# PWM_Drivers.net
KiCad netlist of a schematic drawn in Altium Designer
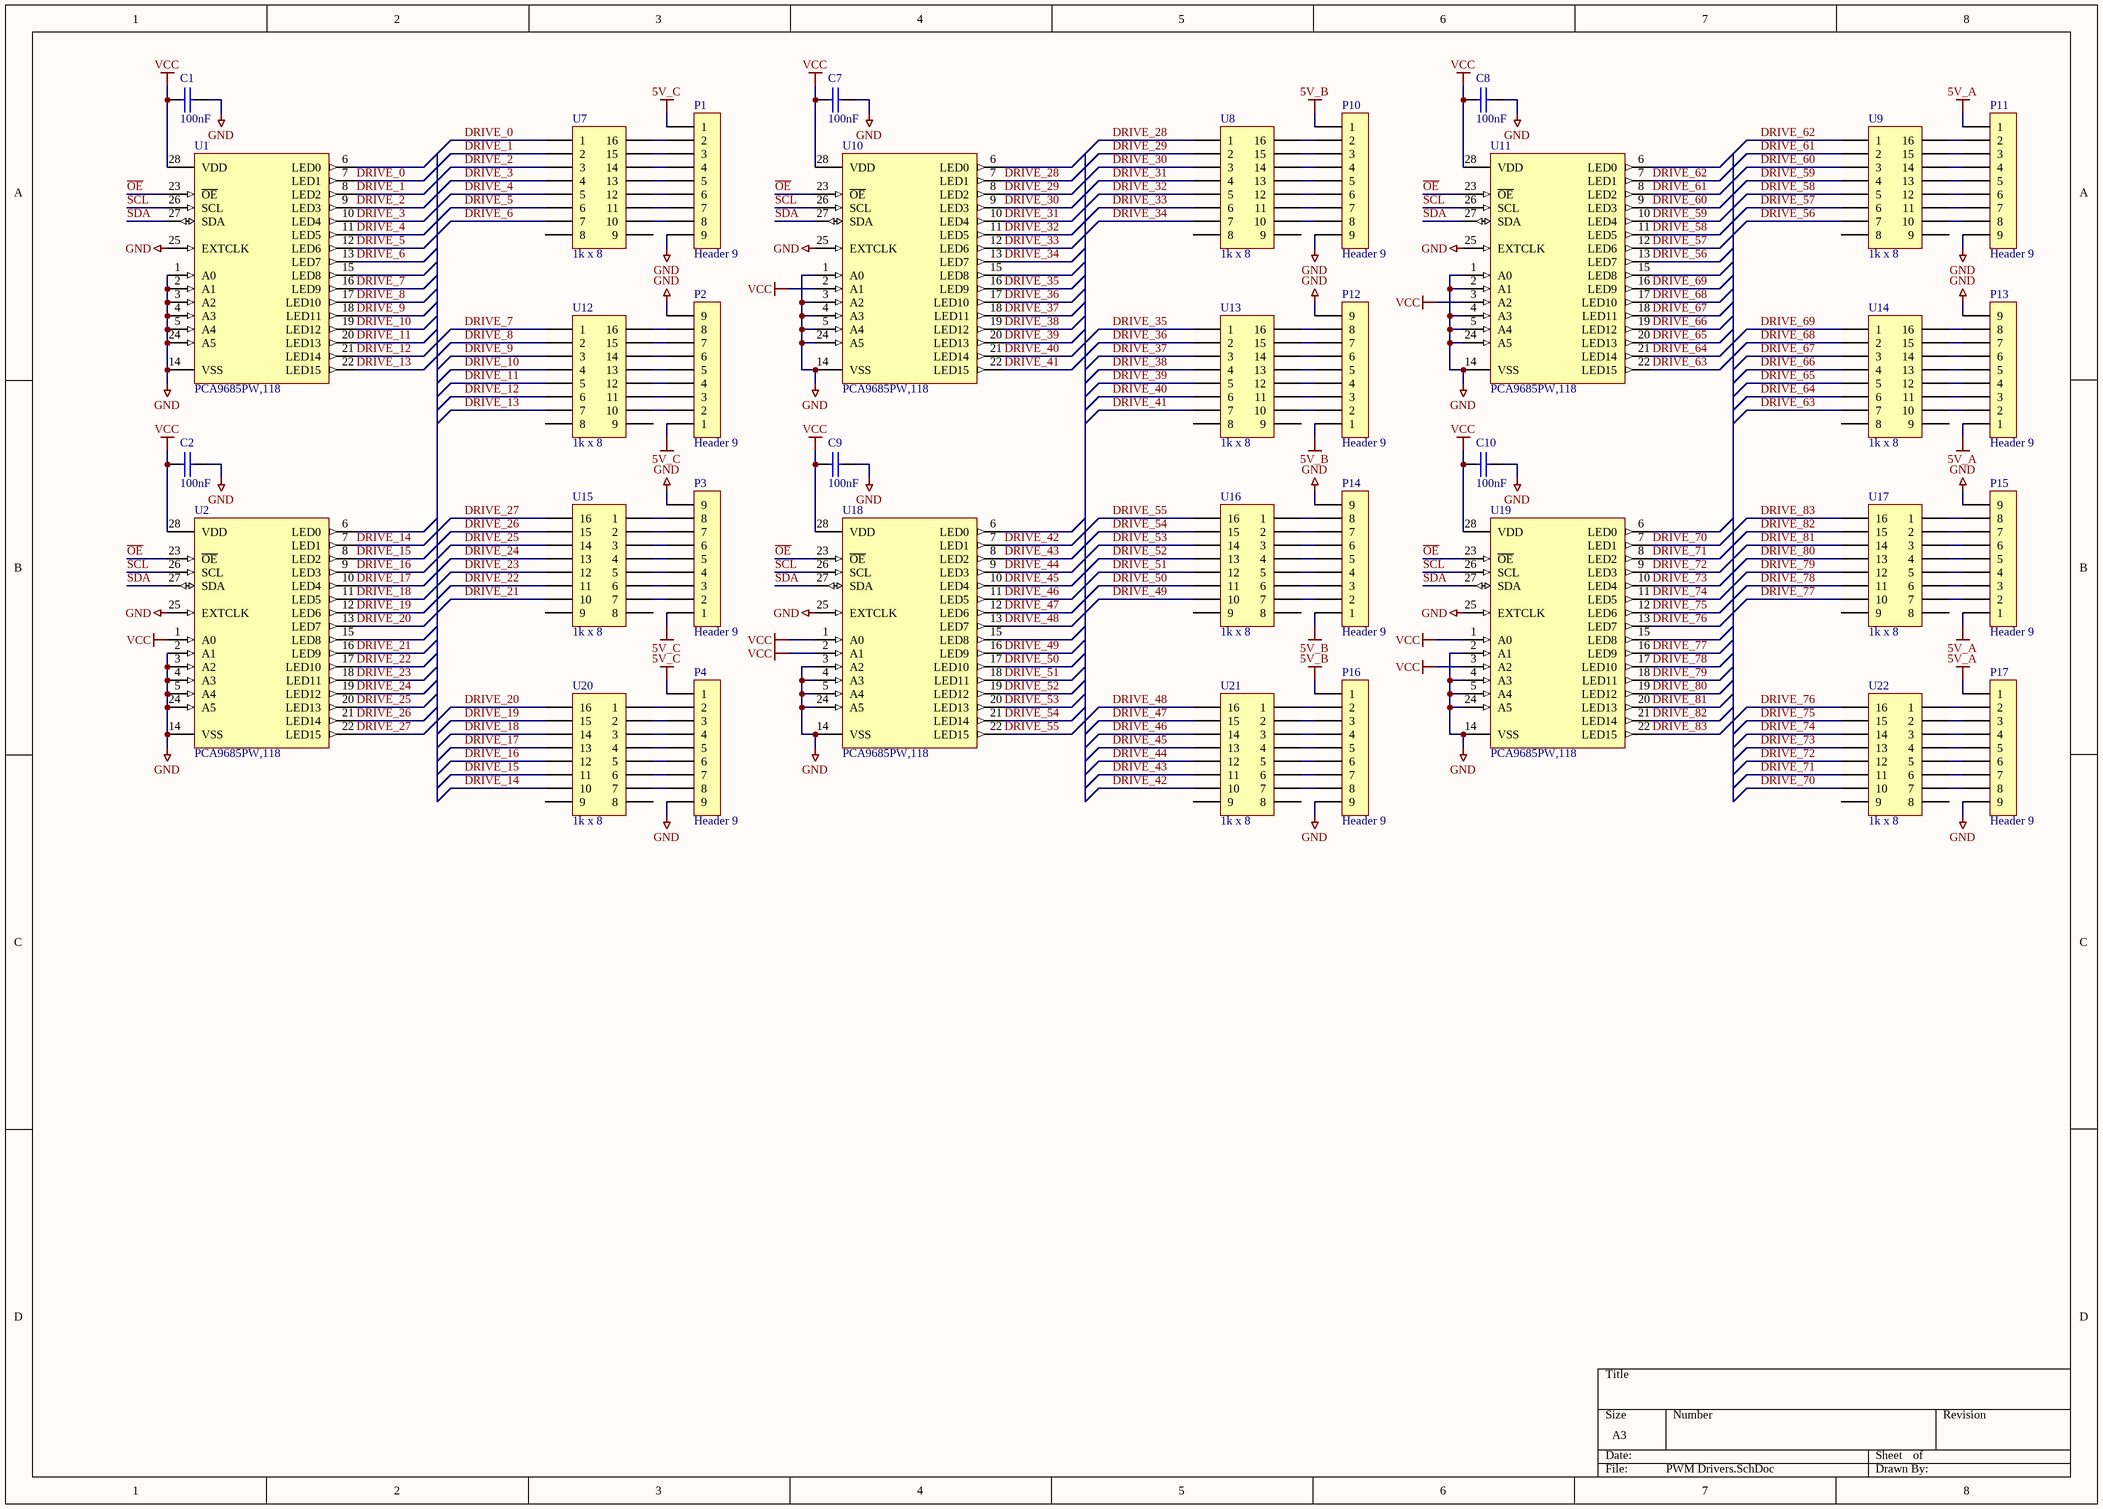
[diagram p0: PWM Drivers.SchDoc]

(export (version "E")
  (design (tool "Eeschema 10.0.6"))
  (components
    (comp (ref "C1")
      (value "100nF")
      (footprint "CAPACITOR 0805")
      (description "CAPACITOR SMD 0603")
      (fields (field (name "MOUSER PART NO.") "81-GCM188R71C104KA7D") (field (name "MANUFACTURER") "Murata"))
      (libsource (lib "Mi-Call Schematic") (part "CAP"))
    )
    (comp (ref "C2")
      (value "100nF")
      (footprint "CAPACITOR 0805")
      (description "CAPACITOR SMD 0603")
      (fields (field (name "MOUSER PART NO.") "81-GCM188R71C104KA7D") (field (name "MANUFACTURER") "Murata"))
      (libsource (lib "Mi-Call Schematic") (part "CAP"))
    )
    (comp (ref "C7")
      (value "100nF")
      (footprint "CAPACITOR 0805")
      (description "CAPACITOR SMD 0603")
      (fields (field (name "MOUSER PART NO.") "81-GCM188R71C104KA7D") (field (name "MANUFACTURER") "Murata"))
      (libsource (lib "Mi-Call Schematic") (part "CAP"))
    )
    (comp (ref "C8")
      (value "100nF")
      (footprint "CAPACITOR 0805")
      (description "CAPACITOR SMD 0603")
      (fields (field (name "MOUSER PART NO.") "81-GCM188R71C104KA7D") (field (name "MANUFACTURER") "Murata"))
      (libsource (lib "Mi-Call Schematic") (part "CAP"))
    )
    (comp (ref "C9")
      (value "100nF")
      (footprint "CAPACITOR 0805")
      (description "CAPACITOR SMD 0603")
      (fields (field (name "MOUSER PART NO.") "81-GCM188R71C104KA7D") (field (name "MANUFACTURER") "Murata"))
      (libsource (lib "Mi-Call Schematic") (part "CAP"))
    )
    (comp (ref "C10")
      (value "100nF")
      (footprint "CAPACITOR 0805")
      (description "CAPACITOR SMD 0603")
      (fields (field (name "MOUSER PART NO.") "81-GCM188R71C104KA7D") (field (name "MANUFACTURER") "Murata"))
      (libsource (lib "Mi-Call Schematic") (part "CAP"))
    )
    (comp (ref "P1")
      (value "Header 9")
      (footprint "SOCKET 1x9")
      (description "Header, 9-Pin")
      (fields (field (name "PUBLISHER") "Altium Limited"))
      (libsource (lib "LED TAIL LIGHTS") (part "Header 9"))
    )
    (comp (ref "P2")
      (value "Header 9")
      (footprint "SOCKET 1x9")
      (description "Header, 9-Pin")
      (fields (field (name "PUBLISHER") "Altium Limited"))
      (libsource (lib "") (part "Header 9_1"))
    )
    (comp (ref "P3")
      (value "Header 9")
      (footprint "SOCKET 1x9")
      (description "Header, 9-Pin")
      (fields (field (name "PUBLISHER") "Altium Limited"))
      (libsource (lib "") (part "Header 9_1"))
    )
    (comp (ref "P4")
      (value "Header 9")
      (footprint "SOCKET 1x9")
      (description "Header, 9-Pin")
      (fields (field (name "PUBLISHER") "Altium Limited"))
      (libsource (lib "LED TAIL LIGHTS") (part "Header 9"))
    )
    (comp (ref "P10")
      (value "Header 9")
      (footprint "SOCKET 1x9")
      (description "Header, 9-Pin")
      (fields (field (name "PUBLISHER") "Altium Limited"))
      (libsource (lib "LED TAIL LIGHTS") (part "Header 9"))
    )
    (comp (ref "P11")
      (value "Header 9")
      (footprint "SOCKET 1x9")
      (description "Header, 9-Pin")
      (fields (field (name "PUBLISHER") "Altium Limited"))
      (libsource (lib "LED TAIL LIGHTS") (part "Header 9"))
    )
    (comp (ref "P12")
      (value "Header 9")
      (footprint "SOCKET 1x9")
      (description "Header, 9-Pin")
      (fields (field (name "PUBLISHER") "Altium Limited"))
      (libsource (lib "") (part "Header 9_1"))
    )
    (comp (ref "P13")
      (value "Header 9")
      (footprint "SOCKET 1x9")
      (description "Header, 9-Pin")
      (fields (field (name "PUBLISHER") "Altium Limited"))
      (libsource (lib "") (part "Header 9_1"))
    )
    (comp (ref "P14")
      (value "Header 9")
      (footprint "SOCKET 1x9")
      (description "Header, 9-Pin")
      (fields (field (name "PUBLISHER") "Altium Limited"))
      (libsource (lib "") (part "Header 9_1"))
    )
    (comp (ref "P15")
      (value "Header 9")
      (footprint "SOCKET 1x9")
      (description "Header, 9-Pin")
      (fields (field (name "PUBLISHER") "Altium Limited"))
      (libsource (lib "") (part "Header 9_1"))
    )
    (comp (ref "P16")
      (value "Header 9")
      (footprint "SOCKET 1x9")
      (description "Header, 9-Pin")
      (fields (field (name "PUBLISHER") "Altium Limited"))
      (libsource (lib "LED TAIL LIGHTS") (part "Header 9"))
    )
    (comp (ref "P17")
      (value "Header 9")
      (footprint "SOCKET 1x9")
      (description "Header, 9-Pin")
      (fields (field (name "PUBLISHER") "Altium Limited"))
      (libsource (lib "LED TAIL LIGHTS") (part "Header 9"))
    )
    (comp (ref "U1")
      (value "PCA9685PW,118")
      (footprint "SSOP28")
      (description "LED Driver IC 16 Output Linear PWM Dimming 25mA 28-TSSOP")
      (fields (field (name "DIGI-KEY_PART_NUMBER") "568-11925-1-ND") (field (name "MF") "NXP USA"))
      (libsource (lib "LED TAIL LIGHTS") (part "PCA9685PW,118"))
    )
    (comp (ref "U2")
      (value "PCA9685PW,118")
      (footprint "SSOP28")
      (description "LED Driver IC 16 Output Linear PWM Dimming 25mA 28-TSSOP")
      (fields (field (name "DIGI-KEY_PART_NUMBER") "568-11925-1-ND") (field (name "MF") "NXP USA"))
      (libsource (lib "LED TAIL LIGHTS") (part "PCA9685PW,118"))
    )
    (comp (ref "U7")
      (value "1k x 8")
      (footprint "DIP 16")
      (description "DIP 16 Resistor Array 8 x 1k")
      (fields (field (name "LCSC PART NUMBER") "C1525823"))
      (libsource (lib "XC Tail Light Driver") (part "ResistorArray"))
    )
    (comp (ref "U8")
      (value "1k x 8")
      (footprint "DIP 16")
      (description "DIP 16 Resistor Array 8 x 1k")
      (fields (field (name "LCSC PART NUMBER") "C1525823"))
      (libsource (lib "XC Tail Light Driver") (part "ResistorArray"))
    )
    (comp (ref "U9")
      (value "1k x 8")
      (footprint "DIP 16")
      (description "DIP 16 Resistor Array 8 x 1k")
      (fields (field (name "LCSC PART NUMBER") "C1525823"))
      (libsource (lib "XC Tail Light Driver") (part "ResistorArray"))
    )
    (comp (ref "U10")
      (value "PCA9685PW,118")
      (footprint "SSOP28")
      (description "LED Driver IC 16 Output Linear PWM Dimming 25mA 28-TSSOP")
      (fields (field (name "DIGI-KEY_PART_NUMBER") "568-11925-1-ND") (field (name "MF") "NXP USA"))
      (libsource (lib "LED TAIL LIGHTS") (part "PCA9685PW,118"))
    )
    (comp (ref "U11")
      (value "PCA9685PW,118")
      (footprint "SSOP28")
      (description "LED Driver IC 16 Output Linear PWM Dimming 25mA 28-TSSOP")
      (fields (field (name "DIGI-KEY_PART_NUMBER") "568-11925-1-ND") (field (name "MF") "NXP USA"))
      (libsource (lib "LED TAIL LIGHTS") (part "PCA9685PW,118"))
    )
    (comp (ref "U12")
      (value "1k x 8")
      (footprint "DIP 16")
      (description "DIP 16 Resistor Array 8 x 1k")
      (fields (field (name "LCSC PART NUMBER") "C1525823"))
      (libsource (lib "XC Tail Light Driver") (part "ResistorArray"))
    )
    (comp (ref "U13")
      (value "1k x 8")
      (footprint "DIP 16")
      (description "DIP 16 Resistor Array 8 x 1k")
      (fields (field (name "LCSC PART NUMBER") "C1525823"))
      (libsource (lib "XC Tail Light Driver") (part "ResistorArray"))
    )
    (comp (ref "U14")
      (value "1k x 8")
      (footprint "DIP 16")
      (description "DIP 16 Resistor Array 8 x 1k")
      (fields (field (name "LCSC PART NUMBER") "C1525823"))
      (libsource (lib "XC Tail Light Driver") (part "ResistorArray"))
    )
    (comp (ref "U15")
      (value "1k x 8")
      (footprint "DIP 16")
      (description "DIP 16 Resistor Array 8 x 1k")
      (fields (field (name "LCSC PART NUMBER") "C1525823"))
      (libsource (lib "") (part "ResistorArray_1"))
    )
    (comp (ref "U16")
      (value "1k x 8")
      (footprint "DIP 16")
      (description "DIP 16 Resistor Array 8 x 1k")
      (fields (field (name "LCSC PART NUMBER") "C1525823"))
      (libsource (lib "") (part "ResistorArray_1"))
    )
    (comp (ref "U17")
      (value "1k x 8")
      (footprint "DIP 16")
      (description "DIP 16 Resistor Array 8 x 1k")
      (fields (field (name "LCSC PART NUMBER") "C1525823"))
      (libsource (lib "") (part "ResistorArray_1"))
    )
    (comp (ref "U18")
      (value "PCA9685PW,118")
      (footprint "SSOP28")
      (description "LED Driver IC 16 Output Linear PWM Dimming 25mA 28-TSSOP")
      (fields (field (name "DIGI-KEY_PART_NUMBER") "568-11925-1-ND") (field (name "MF") "NXP USA"))
      (libsource (lib "LED TAIL LIGHTS") (part "PCA9685PW,118"))
    )
    (comp (ref "U19")
      (value "PCA9685PW,118")
      (footprint "SSOP28")
      (description "LED Driver IC 16 Output Linear PWM Dimming 25mA 28-TSSOP")
      (fields (field (name "DIGI-KEY_PART_NUMBER") "568-11925-1-ND") (field (name "MF") "NXP USA"))
      (libsource (lib "LED TAIL LIGHTS") (part "PCA9685PW,118"))
    )
    (comp (ref "U20")
      (value "1k x 8")
      (footprint "DIP 16")
      (description "DIP 16 Resistor Array 8 x 1k")
      (fields (field (name "LCSC PART NUMBER") "C1525823"))
      (libsource (lib "") (part "ResistorArray_1"))
    )
    (comp (ref "U21")
      (value "1k x 8")
      (footprint "DIP 16")
      (description "DIP 16 Resistor Array 8 x 1k")
      (fields (field (name "LCSC PART NUMBER") "C1525823"))
      (libsource (lib "") (part "ResistorArray_1"))
    )
    (comp (ref "U22")
      (value "1k x 8")
      (footprint "DIP 16")
      (description "DIP 16 Resistor Array 8 x 1k")
      (fields (field (name "LCSC PART NUMBER") "C1525823"))
      (libsource (lib "") (part "ResistorArray_1"))
    )
  )
  (nets
    (net (code "1") (name "/DRIVE_0") (class "Default")
      (node (ref "U1") (pin "7") (pinfunction "LED1_7") (pintype "output"))
      (node (ref "U7") (pin "1") (pinfunction "1_1") (pintype "passive"))
    )
    (net (code "2") (name "/DRIVE_1") (class "Default")
      (node (ref "U1") (pin "8") (pinfunction "LED2_8") (pintype "output"))
      (node (ref "U7") (pin "2") (pinfunction "2_2") (pintype "passive"))
    )
    (net (code "3") (name "/DRIVE_2") (class "Default")
      (node (ref "U1") (pin "9") (pinfunction "LED3_9") (pintype "output"))
      (node (ref "U7") (pin "3") (pinfunction "3_3") (pintype "passive"))
    )
    (net (code "4") (name "/DRIVE_3") (class "Default")
      (node (ref "U1") (pin "10") (pinfunction "LED4_10") (pintype "output"))
      (node (ref "U7") (pin "4") (pinfunction "4_4") (pintype "passive"))
    )
    (net (code "5") (name "/DRIVE_4") (class "Default")
      (node (ref "U1") (pin "11") (pinfunction "LED5_11") (pintype "output"))
      (node (ref "U7") (pin "5") (pinfunction "5_5") (pintype "passive"))
    )
    (net (code "6") (name "/DRIVE_5") (class "Default")
      (node (ref "U1") (pin "12") (pinfunction "LED6_12") (pintype "output"))
      (node (ref "U7") (pin "6") (pinfunction "6_6") (pintype "passive"))
    )
    (net (code "7") (name "/DRIVE_6") (class "Default")
      (node (ref "U1") (pin "13") (pinfunction "LED7_13") (pintype "output"))
      (node (ref "U7") (pin "7") (pinfunction "7_7") (pintype "passive"))
    )
    (net (code "8") (name "/DRIVE_7") (class "Default")
      (node (ref "U1") (pin "16") (pinfunction "LED9_16") (pintype "output"))
      (node (ref "U12") (pin "1") (pinfunction "1_1") (pintype "passive"))
    )
    (net (code "9") (name "/DRIVE_8") (class "Default")
      (node (ref "U1") (pin "17") (pinfunction "LED10_17") (pintype "output"))
      (node (ref "U12") (pin "2") (pinfunction "2_2") (pintype "passive"))
    )
    (net (code "10") (name "/DRIVE_9") (class "Default")
      (node (ref "U1") (pin "18") (pinfunction "LED11_18") (pintype "output"))
      (node (ref "U12") (pin "3") (pinfunction "3_3") (pintype "passive"))
    )
    (net (code "11") (name "/DRIVE_10") (class "Default")
      (node (ref "U1") (pin "19") (pinfunction "LED12_19") (pintype "output"))
      (node (ref "U12") (pin "4") (pinfunction "4_4") (pintype "passive"))
    )
    (net (code "12") (name "/DRIVE_11") (class "Default")
      (node (ref "U1") (pin "20") (pinfunction "LED13_20") (pintype "output"))
      (node (ref "U12") (pin "5") (pinfunction "5_5") (pintype "passive"))
    )
    (net (code "13") (name "/DRIVE_12") (class "Default")
      (node (ref "U1") (pin "21") (pinfunction "LED14_21") (pintype "output"))
      (node (ref "U12") (pin "6") (pinfunction "6_6") (pintype "passive"))
    )
    (net (code "14") (name "/DRIVE_13") (class "Default")
      (node (ref "U1") (pin "22") (pinfunction "LED15_22") (pintype "output"))
      (node (ref "U12") (pin "7") (pinfunction "7_7") (pintype "passive"))
    )
    (net (code "15") (name "/DRIVE_14") (class "Default")
      (node (ref "U2") (pin "7") (pinfunction "LED1_7") (pintype "output"))
      (node (ref "U20") (pin "10") (pinfunction "10_10") (pintype "passive"))
    )
    (net (code "16") (name "/DRIVE_15") (class "Default")
      (node (ref "U2") (pin "8") (pinfunction "LED2_8") (pintype "output"))
      (node (ref "U20") (pin "11") (pinfunction "11_11") (pintype "passive"))
    )
    (net (code "17") (name "/DRIVE_16") (class "Default")
      (node (ref "U2") (pin "9") (pinfunction "LED3_9") (pintype "output"))
      (node (ref "U20") (pin "12") (pinfunction "12_12") (pintype "passive"))
    )
    (net (code "18") (name "/DRIVE_17") (class "Default")
      (node (ref "U2") (pin "10") (pinfunction "LED4_10") (pintype "output"))
      (node (ref "U20") (pin "13") (pinfunction "13_13") (pintype "passive"))
    )
    (net (code "19") (name "/DRIVE_18") (class "Default")
      (node (ref "U2") (pin "11") (pinfunction "LED5_11") (pintype "output"))
      (node (ref "U20") (pin "14") (pinfunction "14_14") (pintype "passive"))
    )
    (net (code "20") (name "/DRIVE_19") (class "Default")
      (node (ref "U2") (pin "12") (pinfunction "LED6_12") (pintype "output"))
      (node (ref "U20") (pin "15") (pinfunction "15_15") (pintype "passive"))
    )
    (net (code "21") (name "/DRIVE_20") (class "Default")
      (node (ref "U2") (pin "13") (pinfunction "LED7_13") (pintype "output"))
      (node (ref "U20") (pin "16") (pinfunction "16_16") (pintype "passive"))
    )
    (net (code "22") (name "/DRIVE_21") (class "Default")
      (node (ref "U15") (pin "10") (pinfunction "10_10") (pintype "passive"))
      (node (ref "U2") (pin "16") (pinfunction "LED9_16") (pintype "output"))
    )
    (net (code "23") (name "/DRIVE_22") (class "Default")
      (node (ref "U15") (pin "11") (pinfunction "11_11") (pintype "passive"))
      (node (ref "U2") (pin "17") (pinfunction "LED10_17") (pintype "output"))
    )
    (net (code "24") (name "/DRIVE_23") (class "Default")
      (node (ref "U15") (pin "12") (pinfunction "12_12") (pintype "passive"))
      (node (ref "U2") (pin "18") (pinfunction "LED11_18") (pintype "output"))
    )
    (net (code "25") (name "/DRIVE_24") (class "Default")
      (node (ref "U15") (pin "13") (pinfunction "13_13") (pintype "passive"))
      (node (ref "U2") (pin "19") (pinfunction "LED12_19") (pintype "output"))
    )
    (net (code "26") (name "/DRIVE_25") (class "Default")
      (node (ref "U15") (pin "14") (pinfunction "14_14") (pintype "passive"))
      (node (ref "U2") (pin "20") (pinfunction "LED13_20") (pintype "output"))
    )
    (net (code "27") (name "/DRIVE_26") (class "Default")
      (node (ref "U15") (pin "15") (pinfunction "15_15") (pintype "passive"))
      (node (ref "U2") (pin "21") (pinfunction "LED14_21") (pintype "output"))
    )
    (net (code "28") (name "/DRIVE_27") (class "Default")
      (node (ref "U15") (pin "16") (pinfunction "16_16") (pintype "passive"))
      (node (ref "U2") (pin "22") (pinfunction "LED15_22") (pintype "output"))
    )
    (net (code "29") (name "/DRIVE_28") (class "Default")
      (node (ref "U10") (pin "7") (pinfunction "LED1_7") (pintype "output"))
      (node (ref "U8") (pin "1") (pinfunction "1_1") (pintype "passive"))
    )
    (net (code "30") (name "/DRIVE_29") (class "Default")
      (node (ref "U10") (pin "8") (pinfunction "LED2_8") (pintype "output"))
      (node (ref "U8") (pin "2") (pinfunction "2_2") (pintype "passive"))
    )
    (net (code "31") (name "/DRIVE_30") (class "Default")
      (node (ref "U10") (pin "9") (pinfunction "LED3_9") (pintype "output"))
      (node (ref "U8") (pin "3") (pinfunction "3_3") (pintype "passive"))
    )
    (net (code "32") (name "/DRIVE_31") (class "Default")
      (node (ref "U10") (pin "10") (pinfunction "LED4_10") (pintype "output"))
      (node (ref "U8") (pin "4") (pinfunction "4_4") (pintype "passive"))
    )
    (net (code "33") (name "/DRIVE_32") (class "Default")
      (node (ref "U10") (pin "11") (pinfunction "LED5_11") (pintype "output"))
      (node (ref "U8") (pin "5") (pinfunction "5_5") (pintype "passive"))
    )
    (net (code "34") (name "/DRIVE_33") (class "Default")
      (node (ref "U10") (pin "12") (pinfunction "LED6_12") (pintype "output"))
      (node (ref "U8") (pin "6") (pinfunction "6_6") (pintype "passive"))
    )
    (net (code "35") (name "/DRIVE_34") (class "Default")
      (node (ref "U10") (pin "13") (pinfunction "LED7_13") (pintype "output"))
      (node (ref "U8") (pin "7") (pinfunction "7_7") (pintype "passive"))
    )
    (net (code "36") (name "/DRIVE_35") (class "Default")
      (node (ref "U10") (pin "16") (pinfunction "LED9_16") (pintype "output"))
      (node (ref "U13") (pin "1") (pinfunction "1_1") (pintype "passive"))
    )
    (net (code "37") (name "/DRIVE_36") (class "Default")
      (node (ref "U10") (pin "17") (pinfunction "LED10_17") (pintype "output"))
      (node (ref "U13") (pin "2") (pinfunction "2_2") (pintype "passive"))
    )
    (net (code "38") (name "/DRIVE_37") (class "Default")
      (node (ref "U10") (pin "18") (pinfunction "LED11_18") (pintype "output"))
      (node (ref "U13") (pin "3") (pinfunction "3_3") (pintype "passive"))
    )
    (net (code "39") (name "/DRIVE_38") (class "Default")
      (node (ref "U10") (pin "19") (pinfunction "LED12_19") (pintype "output"))
      (node (ref "U13") (pin "4") (pinfunction "4_4") (pintype "passive"))
    )
    (net (code "40") (name "/DRIVE_39") (class "Default")
      (node (ref "U10") (pin "20") (pinfunction "LED13_20") (pintype "output"))
      (node (ref "U13") (pin "5") (pinfunction "5_5") (pintype "passive"))
    )
    (net (code "41") (name "/DRIVE_40") (class "Default")
      (node (ref "U10") (pin "21") (pinfunction "LED14_21") (pintype "output"))
      (node (ref "U13") (pin "6") (pinfunction "6_6") (pintype "passive"))
    )
    (net (code "42") (name "/DRIVE_41") (class "Default")
      (node (ref "U10") (pin "22") (pinfunction "LED15_22") (pintype "output"))
      (node (ref "U13") (pin "7") (pinfunction "7_7") (pintype "passive"))
    )
    (net (code "43") (name "/DRIVE_42") (class "Default")
      (node (ref "U18") (pin "7") (pinfunction "LED1_7") (pintype "output"))
      (node (ref "U21") (pin "10") (pinfunction "10_10") (pintype "passive"))
    )
    (net (code "44") (name "/DRIVE_43") (class "Default")
      (node (ref "U18") (pin "8") (pinfunction "LED2_8") (pintype "output"))
      (node (ref "U21") (pin "11") (pinfunction "11_11") (pintype "passive"))
    )
    (net (code "45") (name "/DRIVE_44") (class "Default")
      (node (ref "U18") (pin "9") (pinfunction "LED3_9") (pintype "output"))
      (node (ref "U21") (pin "12") (pinfunction "12_12") (pintype "passive"))
    )
    (net (code "46") (name "/DRIVE_45") (class "Default")
      (node (ref "U18") (pin "10") (pinfunction "LED4_10") (pintype "output"))
      (node (ref "U21") (pin "13") (pinfunction "13_13") (pintype "passive"))
    )
    (net (code "47") (name "/DRIVE_46") (class "Default")
      (node (ref "U18") (pin "11") (pinfunction "LED5_11") (pintype "output"))
      (node (ref "U21") (pin "14") (pinfunction "14_14") (pintype "passive"))
    )
    (net (code "48") (name "/DRIVE_47") (class "Default")
      (node (ref "U18") (pin "12") (pinfunction "LED6_12") (pintype "output"))
      (node (ref "U21") (pin "15") (pinfunction "15_15") (pintype "passive"))
    )
    (net (code "49") (name "/DRIVE_48") (class "Default")
      (node (ref "U18") (pin "13") (pinfunction "LED7_13") (pintype "output"))
      (node (ref "U21") (pin "16") (pinfunction "16_16") (pintype "passive"))
    )
    (net (code "50") (name "/DRIVE_49") (class "Default")
      (node (ref "U16") (pin "10") (pinfunction "10_10") (pintype "passive"))
      (node (ref "U18") (pin "16") (pinfunction "LED9_16") (pintype "output"))
    )
    (net (code "51") (name "/DRIVE_50") (class "Default")
      (node (ref "U16") (pin "11") (pinfunction "11_11") (pintype "passive"))
      (node (ref "U18") (pin "17") (pinfunction "LED10_17") (pintype "output"))
    )
    (net (code "52") (name "/DRIVE_51") (class "Default")
      (node (ref "U16") (pin "12") (pinfunction "12_12") (pintype "passive"))
      (node (ref "U18") (pin "18") (pinfunction "LED11_18") (pintype "output"))
    )
    (net (code "53") (name "/DRIVE_52") (class "Default")
      (node (ref "U16") (pin "13") (pinfunction "13_13") (pintype "passive"))
      (node (ref "U18") (pin "19") (pinfunction "LED12_19") (pintype "output"))
    )
    (net (code "54") (name "/DRIVE_53") (class "Default")
      (node (ref "U16") (pin "14") (pinfunction "14_14") (pintype "passive"))
      (node (ref "U18") (pin "20") (pinfunction "LED13_20") (pintype "output"))
    )
    (net (code "55") (name "/DRIVE_54") (class "Default")
      (node (ref "U16") (pin "15") (pinfunction "15_15") (pintype "passive"))
      (node (ref "U18") (pin "21") (pinfunction "LED14_21") (pintype "output"))
    )
    (net (code "56") (name "/DRIVE_55") (class "Default")
      (node (ref "U16") (pin "16") (pinfunction "16_16") (pintype "passive"))
      (node (ref "U18") (pin "22") (pinfunction "LED15_22") (pintype "output"))
    )
    (net (code "57") (name "/DRIVE_56") (class "Default")
      (node (ref "U11") (pin "13") (pinfunction "LED7_13") (pintype "output"))
      (node (ref "U9") (pin "7") (pinfunction "7_7") (pintype "passive"))
    )
    (net (code "58") (name "/DRIVE_57") (class "Default")
      (node (ref "U11") (pin "12") (pinfunction "LED6_12") (pintype "output"))
      (node (ref "U9") (pin "6") (pinfunction "6_6") (pintype "passive"))
    )
    (net (code "59") (name "/DRIVE_58") (class "Default")
      (node (ref "U11") (pin "11") (pinfunction "LED5_11") (pintype "output"))
      (node (ref "U9") (pin "5") (pinfunction "5_5") (pintype "passive"))
    )
    (net (code "60") (name "/DRIVE_59") (class "Default")
      (node (ref "U11") (pin "10") (pinfunction "LED4_10") (pintype "output"))
      (node (ref "U9") (pin "4") (pinfunction "4_4") (pintype "passive"))
    )
    (net (code "61") (name "/DRIVE_60") (class "Default")
      (node (ref "U11") (pin "9") (pinfunction "LED3_9") (pintype "output"))
      (node (ref "U9") (pin "3") (pinfunction "3_3") (pintype "passive"))
    )
    (net (code "62") (name "/DRIVE_61") (class "Default")
      (node (ref "U11") (pin "8") (pinfunction "LED2_8") (pintype "output"))
      (node (ref "U9") (pin "2") (pinfunction "2_2") (pintype "passive"))
    )
    (net (code "63") (name "/DRIVE_62") (class "Default")
      (node (ref "U11") (pin "7") (pinfunction "LED1_7") (pintype "output"))
      (node (ref "U9") (pin "1") (pinfunction "1_1") (pintype "passive"))
    )
    (net (code "64") (name "/DRIVE_63") (class "Default")
      (node (ref "U11") (pin "22") (pinfunction "LED15_22") (pintype "output"))
      (node (ref "U14") (pin "7") (pinfunction "7_7") (pintype "passive"))
    )
    (net (code "65") (name "/DRIVE_64") (class "Default")
      (node (ref "U11") (pin "21") (pinfunction "LED14_21") (pintype "output"))
      (node (ref "U14") (pin "6") (pinfunction "6_6") (pintype "passive"))
    )
    (net (code "66") (name "/DRIVE_65") (class "Default")
      (node (ref "U11") (pin "20") (pinfunction "LED13_20") (pintype "output"))
      (node (ref "U14") (pin "5") (pinfunction "5_5") (pintype "passive"))
    )
    (net (code "67") (name "/DRIVE_66") (class "Default")
      (node (ref "U11") (pin "19") (pinfunction "LED12_19") (pintype "output"))
      (node (ref "U14") (pin "4") (pinfunction "4_4") (pintype "passive"))
    )
    (net (code "68") (name "/DRIVE_67") (class "Default")
      (node (ref "U11") (pin "18") (pinfunction "LED11_18") (pintype "output"))
      (node (ref "U14") (pin "3") (pinfunction "3_3") (pintype "passive"))
    )
    (net (code "69") (name "/DRIVE_68") (class "Default")
      (node (ref "U11") (pin "17") (pinfunction "LED10_17") (pintype "output"))
      (node (ref "U14") (pin "2") (pinfunction "2_2") (pintype "passive"))
    )
    (net (code "70") (name "/DRIVE_69") (class "Default")
      (node (ref "U11") (pin "16") (pinfunction "LED9_16") (pintype "output"))
      (node (ref "U14") (pin "1") (pinfunction "1_1") (pintype "passive"))
    )
    (net (code "71") (name "/DRIVE_70") (class "Default")
      (node (ref "U19") (pin "7") (pinfunction "LED1_7") (pintype "output"))
      (node (ref "U22") (pin "10") (pinfunction "10_10") (pintype "passive"))
    )
    (net (code "72") (name "/DRIVE_71") (class "Default")
      (node (ref "U19") (pin "8") (pinfunction "LED2_8") (pintype "output"))
      (node (ref "U22") (pin "11") (pinfunction "11_11") (pintype "passive"))
    )
    (net (code "73") (name "/DRIVE_72") (class "Default")
      (node (ref "U19") (pin "9") (pinfunction "LED3_9") (pintype "output"))
      (node (ref "U22") (pin "12") (pinfunction "12_12") (pintype "passive"))
    )
    (net (code "74") (name "/DRIVE_73") (class "Default")
      (node (ref "U19") (pin "10") (pinfunction "LED4_10") (pintype "output"))
      (node (ref "U22") (pin "13") (pinfunction "13_13") (pintype "passive"))
    )
    (net (code "75") (name "/DRIVE_74") (class "Default")
      (node (ref "U19") (pin "11") (pinfunction "LED5_11") (pintype "output"))
      (node (ref "U22") (pin "14") (pinfunction "14_14") (pintype "passive"))
    )
    (net (code "76") (name "/DRIVE_75") (class "Default")
      (node (ref "U19") (pin "12") (pinfunction "LED6_12") (pintype "output"))
      (node (ref "U22") (pin "15") (pinfunction "15_15") (pintype "passive"))
    )
    (net (code "77") (name "/DRIVE_76") (class "Default")
      (node (ref "U19") (pin "13") (pinfunction "LED7_13") (pintype "output"))
      (node (ref "U22") (pin "16") (pinfunction "16_16") (pintype "passive"))
    )
    (net (code "78") (name "/DRIVE_77") (class "Default")
      (node (ref "U17") (pin "10") (pinfunction "10_10") (pintype "passive"))
      (node (ref "U19") (pin "16") (pinfunction "LED9_16") (pintype "output"))
    )
    (net (code "79") (name "/DRIVE_78") (class "Default")
      (node (ref "U17") (pin "11") (pinfunction "11_11") (pintype "passive"))
      (node (ref "U19") (pin "17") (pinfunction "LED10_17") (pintype "output"))
    )
    (net (code "80") (name "/DRIVE_79") (class "Default")
      (node (ref "U17") (pin "12") (pinfunction "12_12") (pintype "passive"))
      (node (ref "U19") (pin "18") (pinfunction "LED11_18") (pintype "output"))
    )
    (net (code "81") (name "/DRIVE_80") (class "Default")
      (node (ref "U17") (pin "13") (pinfunction "13_13") (pintype "passive"))
      (node (ref "U19") (pin "19") (pinfunction "LED12_19") (pintype "output"))
    )
    (net (code "82") (name "/DRIVE_81") (class "Default")
      (node (ref "U17") (pin "14") (pinfunction "14_14") (pintype "passive"))
      (node (ref "U19") (pin "20") (pinfunction "LED13_20") (pintype "output"))
    )
    (net (code "83") (name "/DRIVE_82") (class "Default")
      (node (ref "U17") (pin "15") (pinfunction "15_15") (pintype "passive"))
      (node (ref "U19") (pin "21") (pinfunction "LED14_21") (pintype "output"))
    )
    (net (code "84") (name "/DRIVE_83") (class "Default")
      (node (ref "U17") (pin "16") (pinfunction "16_16") (pintype "passive"))
      (node (ref "U19") (pin "22") (pinfunction "LED15_22") (pintype "output"))
    )
    (net (code "85") (name "/SCL") (class "Default")
      (node (ref "U1") (pin "26") (pinfunction "SCL_26") (pintype "input"))
      (node (ref "U10") (pin "26") (pinfunction "SCL_26") (pintype "input"))
      (node (ref "U11") (pin "26") (pinfunction "SCL_26") (pintype "input"))
      (node (ref "U18") (pin "26") (pinfunction "SCL_26") (pintype "input"))
      (node (ref "U19") (pin "26") (pinfunction "SCL_26") (pintype "input"))
      (node (ref "U2") (pin "26") (pinfunction "SCL_26") (pintype "input"))
    )
    (net (code "86") (name "/SDA") (class "Default")
      (node (ref "U1") (pin "27") (pinfunction "SDA_27") (pintype "bidirectional"))
      (node (ref "U10") (pin "27") (pinfunction "SDA_27") (pintype "bidirectional"))
      (node (ref "U11") (pin "27") (pinfunction "SDA_27") (pintype "bidirectional"))
      (node (ref "U18") (pin "27") (pinfunction "SDA_27") (pintype "bidirectional"))
      (node (ref "U19") (pin "27") (pinfunction "SDA_27") (pintype "bidirectional"))
      (node (ref "U2") (pin "27") (pinfunction "SDA_27") (pintype "bidirectional"))
    )
    (net (code "87") (name "/~{OE}") (class "Default")
      (node (ref "U1") (pin "23") (pinfunction "~{OE}_23") (pintype "input"))
      (node (ref "U10") (pin "23") (pinfunction "~{OE}_23") (pintype "input"))
      (node (ref "U11") (pin "23") (pinfunction "~{OE}_23") (pintype "input"))
      (node (ref "U18") (pin "23") (pinfunction "~{OE}_23") (pintype "input"))
      (node (ref "U19") (pin "23") (pinfunction "~{OE}_23") (pintype "input"))
      (node (ref "U2") (pin "23") (pinfunction "~{OE}_23") (pintype "input"))
    )
    (net (code "88") (name "5V_A") (class "Default")
      (node (ref "P11") (pin "1") (pinfunction "1_1") (pintype "passive"))
      (node (ref "P13") (pin "1") (pinfunction "1_1") (pintype "passive"))
      (node (ref "P15") (pin "1") (pinfunction "1_1") (pintype "passive"))
      (node (ref "P17") (pin "1") (pinfunction "1_1") (pintype "passive"))
    )
    (net (code "89") (name "5V_B") (class "Default")
      (node (ref "P10") (pin "1") (pinfunction "1_1") (pintype "passive"))
      (node (ref "P12") (pin "1") (pinfunction "1_1") (pintype "passive"))
      (node (ref "P14") (pin "1") (pinfunction "1_1") (pintype "passive"))
      (node (ref "P16") (pin "1") (pinfunction "1_1") (pintype "passive"))
    )
    (net (code "90") (name "5V_C") (class "Default")
      (node (ref "P1") (pin "1") (pinfunction "1_1") (pintype "passive"))
      (node (ref "P2") (pin "1") (pinfunction "1_1") (pintype "passive"))
      (node (ref "P3") (pin "1") (pinfunction "1_1") (pintype "passive"))
      (node (ref "P4") (pin "1") (pinfunction "1_1") (pintype "passive"))
    )
    (net (code "91") (name "GND") (class "Default")
      (node (ref "C1") (pin "2") (pinfunction "2_2") (pintype "passive"))
      (node (ref "C10") (pin "2") (pinfunction "2_2") (pintype "passive"))
      (node (ref "C2") (pin "2") (pinfunction "2_2") (pintype "passive"))
      (node (ref "C7") (pin "2") (pinfunction "2_2") (pintype "passive"))
      (node (ref "C8") (pin "2") (pinfunction "2_2") (pintype "passive"))
      (node (ref "C9") (pin "2") (pinfunction "2_2") (pintype "passive"))
      (node (ref "P1") (pin "9") (pinfunction "9_9") (pintype "passive"))
      (node (ref "P10") (pin "9") (pinfunction "9_9") (pintype "passive"))
      (node (ref "P11") (pin "9") (pinfunction "9_9") (pintype "passive"))
      (node (ref "P12") (pin "9") (pinfunction "9_9") (pintype "passive"))
      (node (ref "P13") (pin "9") (pinfunction "9_9") (pintype "passive"))
      (node (ref "P14") (pin "9") (pinfunction "9_9") (pintype "passive"))
      (node (ref "P15") (pin "9") (pinfunction "9_9") (pintype "passive"))
      (node (ref "P16") (pin "9") (pinfunction "9_9") (pintype "passive"))
      (node (ref "P17") (pin "9") (pinfunction "9_9") (pintype "passive"))
      (node (ref "P2") (pin "9") (pinfunction "9_9") (pintype "passive"))
      (node (ref "P3") (pin "9") (pinfunction "9_9") (pintype "passive"))
      (node (ref "P4") (pin "9") (pinfunction "9_9") (pintype "passive"))
      (node (ref "U1") (pin "1") (pinfunction "A0_1") (pintype "input"))
      (node (ref "U1") (pin "14") (pinfunction "VSS_14") (pintype "passive"))
      (node (ref "U1") (pin "2") (pinfunction "A1_2") (pintype "input"))
      (node (ref "U1") (pin "24") (pinfunction "A5_24") (pintype "input"))
      (node (ref "U1") (pin "25") (pinfunction "EXTCLK_25") (pintype "input"))
      (node (ref "U1") (pin "3") (pinfunction "A2_3") (pintype "input"))
      (node (ref "U1") (pin "4") (pinfunction "A3_4") (pintype "input"))
      (node (ref "U1") (pin "5") (pinfunction "A4_5") (pintype "input"))
      (node (ref "U10") (pin "1") (pinfunction "A0_1") (pintype "input"))
      (node (ref "U10") (pin "14") (pinfunction "VSS_14") (pintype "passive"))
      (node (ref "U10") (pin "24") (pinfunction "A5_24") (pintype "input"))
      (node (ref "U10") (pin "25") (pinfunction "EXTCLK_25") (pintype "input"))
      (node (ref "U10") (pin "3") (pinfunction "A2_3") (pintype "input"))
      (node (ref "U10") (pin "4") (pinfunction "A3_4") (pintype "input"))
      (node (ref "U10") (pin "5") (pinfunction "A4_5") (pintype "input"))
      (node (ref "U11") (pin "1") (pinfunction "A0_1") (pintype "input"))
      (node (ref "U11") (pin "14") (pinfunction "VSS_14") (pintype "passive"))
      (node (ref "U11") (pin "2") (pinfunction "A1_2") (pintype "input"))
      (node (ref "U11") (pin "24") (pinfunction "A5_24") (pintype "input"))
      (node (ref "U11") (pin "25") (pinfunction "EXTCLK_25") (pintype "input"))
      (node (ref "U11") (pin "4") (pinfunction "A3_4") (pintype "input"))
      (node (ref "U11") (pin "5") (pinfunction "A4_5") (pintype "input"))
      (node (ref "U18") (pin "14") (pinfunction "VSS_14") (pintype "passive"))
      (node (ref "U18") (pin "24") (pinfunction "A5_24") (pintype "input"))
      (node (ref "U18") (pin "25") (pinfunction "EXTCLK_25") (pintype "input"))
      (node (ref "U18") (pin "3") (pinfunction "A2_3") (pintype "input"))
      (node (ref "U18") (pin "4") (pinfunction "A3_4") (pintype "input"))
      (node (ref "U18") (pin "5") (pinfunction "A4_5") (pintype "input"))
      (node (ref "U19") (pin "14") (pinfunction "VSS_14") (pintype "passive"))
      (node (ref "U19") (pin "2") (pinfunction "A1_2") (pintype "input"))
      (node (ref "U19") (pin "24") (pinfunction "A5_24") (pintype "input"))
      (node (ref "U19") (pin "25") (pinfunction "EXTCLK_25") (pintype "input"))
      (node (ref "U19") (pin "4") (pinfunction "A3_4") (pintype "input"))
      (node (ref "U19") (pin "5") (pinfunction "A4_5") (pintype "input"))
      (node (ref "U2") (pin "14") (pinfunction "VSS_14") (pintype "passive"))
      (node (ref "U2") (pin "2") (pinfunction "A1_2") (pintype "input"))
      (node (ref "U2") (pin "24") (pinfunction "A5_24") (pintype "input"))
      (node (ref "U2") (pin "25") (pinfunction "EXTCLK_25") (pintype "input"))
      (node (ref "U2") (pin "3") (pinfunction "A2_3") (pintype "input"))
      (node (ref "U2") (pin "4") (pinfunction "A3_4") (pintype "input"))
      (node (ref "U2") (pin "5") (pinfunction "A4_5") (pintype "input"))
    )
    (net (code "92") (name "Net-(P1-Pad2)") (class "Default")
      (node (ref "P1") (pin "2") (pinfunction "2_2") (pintype "passive"))
      (node (ref "U7") (pin "16") (pinfunction "16_16") (pintype "passive"))
    )
    (net (code "93") (name "Net-(P1-Pad3)") (class "Default")
      (node (ref "P1") (pin "3") (pinfunction "3_3") (pintype "passive"))
      (node (ref "U7") (pin "15") (pinfunction "15_15") (pintype "passive"))
    )
    (net (code "94") (name "Net-(P1-Pad4)") (class "Default")
      (node (ref "P1") (pin "4") (pinfunction "4_4") (pintype "passive"))
      (node (ref "U7") (pin "14") (pinfunction "14_14") (pintype "passive"))
    )
    (net (code "95") (name "Net-(P1-Pad5)") (class "Default")
      (node (ref "P1") (pin "5") (pinfunction "5_5") (pintype "passive"))
      (node (ref "U7") (pin "13") (pinfunction "13_13") (pintype "passive"))
    )
    (net (code "96") (name "Net-(P1-Pad6)") (class "Default")
      (node (ref "P1") (pin "6") (pinfunction "6_6") (pintype "passive"))
      (node (ref "U7") (pin "12") (pinfunction "12_12") (pintype "passive"))
    )
    (net (code "97") (name "Net-(P1-Pad7)") (class "Default")
      (node (ref "P1") (pin "7") (pinfunction "7_7") (pintype "passive"))
      (node (ref "U7") (pin "11") (pinfunction "11_11") (pintype "passive"))
    )
    (net (code "98") (name "Net-(P1-Pad8)") (class "Default")
      (node (ref "P1") (pin "8") (pinfunction "8_8") (pintype "passive"))
      (node (ref "U7") (pin "10") (pinfunction "10_10") (pintype "passive"))
    )
    (net (code "99") (name "Net-(P2-Pad2)") (class "Default")
      (node (ref "P2") (pin "2") (pinfunction "2_2") (pintype "passive"))
      (node (ref "U12") (pin "10") (pinfunction "10_10") (pintype "passive"))
    )
    (net (code "100") (name "Net-(P2-Pad3)") (class "Default")
      (node (ref "P2") (pin "3") (pinfunction "3_3") (pintype "passive"))
      (node (ref "U12") (pin "11") (pinfunction "11_11") (pintype "passive"))
    )
    (net (code "101") (name "Net-(P2-Pad4)") (class "Default")
      (node (ref "P2") (pin "4") (pinfunction "4_4") (pintype "passive"))
      (node (ref "U12") (pin "12") (pinfunction "12_12") (pintype "passive"))
    )
    (net (code "102") (name "Net-(P2-Pad5)") (class "Default")
      (node (ref "P2") (pin "5") (pinfunction "5_5") (pintype "passive"))
      (node (ref "U12") (pin "13") (pinfunction "13_13") (pintype "passive"))
    )
    (net (code "103") (name "Net-(P2-Pad6)") (class "Default")
      (node (ref "P2") (pin "6") (pinfunction "6_6") (pintype "passive"))
      (node (ref "U12") (pin "14") (pinfunction "14_14") (pintype "passive"))
    )
    (net (code "104") (name "Net-(P2-Pad7)") (class "Default")
      (node (ref "P2") (pin "7") (pinfunction "7_7") (pintype "passive"))
      (node (ref "U12") (pin "15") (pinfunction "15_15") (pintype "passive"))
    )
    (net (code "105") (name "Net-(P2-Pad8)") (class "Default")
      (node (ref "P2") (pin "8") (pinfunction "8_8") (pintype "passive"))
      (node (ref "U12") (pin "16") (pinfunction "16_16") (pintype "passive"))
    )
    (net (code "106") (name "Net-(P3-Pad2)") (class "Default")
      (node (ref "P3") (pin "2") (pinfunction "2_2") (pintype "passive"))
      (node (ref "U15") (pin "7") (pinfunction "7_7") (pintype "passive"))
    )
    (net (code "107") (name "Net-(P3-Pad3)") (class "Default")
      (node (ref "P3") (pin "3") (pinfunction "3_3") (pintype "passive"))
      (node (ref "U15") (pin "6") (pinfunction "6_6") (pintype "passive"))
    )
    (net (code "108") (name "Net-(P3-Pad4)") (class "Default")
      (node (ref "P3") (pin "4") (pinfunction "4_4") (pintype "passive"))
      (node (ref "U15") (pin "5") (pinfunction "5_5") (pintype "passive"))
    )
    (net (code "109") (name "Net-(P3-Pad5)") (class "Default")
      (node (ref "P3") (pin "5") (pinfunction "5_5") (pintype "passive"))
      (node (ref "U15") (pin "4") (pinfunction "4_4") (pintype "passive"))
    )
    (net (code "110") (name "Net-(P3-Pad6)") (class "Default")
      (node (ref "P3") (pin "6") (pinfunction "6_6") (pintype "passive"))
      (node (ref "U15") (pin "3") (pinfunction "3_3") (pintype "passive"))
    )
    (net (code "111") (name "Net-(P3-Pad7)") (class "Default")
      (node (ref "P3") (pin "7") (pinfunction "7_7") (pintype "passive"))
      (node (ref "U15") (pin "2") (pinfunction "2_2") (pintype "passive"))
    )
    (net (code "112") (name "Net-(P3-Pad8)") (class "Default")
      (node (ref "P3") (pin "8") (pinfunction "8_8") (pintype "passive"))
      (node (ref "U15") (pin "1") (pinfunction "1_1") (pintype "passive"))
    )
    (net (code "113") (name "Net-(P4-Pad2)") (class "Default")
      (node (ref "P4") (pin "2") (pinfunction "2_2") (pintype "passive"))
      (node (ref "U20") (pin "1") (pinfunction "1_1") (pintype "passive"))
    )
    (net (code "114") (name "Net-(P4-Pad3)") (class "Default")
      (node (ref "P4") (pin "3") (pinfunction "3_3") (pintype "passive"))
      (node (ref "U20") (pin "2") (pinfunction "2_2") (pintype "passive"))
    )
    (net (code "115") (name "Net-(P4-Pad4)") (class "Default")
      (node (ref "P4") (pin "4") (pinfunction "4_4") (pintype "passive"))
      (node (ref "U20") (pin "3") (pinfunction "3_3") (pintype "passive"))
    )
    (net (code "116") (name "Net-(P4-Pad5)") (class "Default")
      (node (ref "P4") (pin "5") (pinfunction "5_5") (pintype "passive"))
      (node (ref "U20") (pin "4") (pinfunction "4_4") (pintype "passive"))
    )
    (net (code "117") (name "Net-(P4-Pad6)") (class "Default")
      (node (ref "P4") (pin "6") (pinfunction "6_6") (pintype "passive"))
      (node (ref "U20") (pin "5") (pinfunction "5_5") (pintype "passive"))
    )
    (net (code "118") (name "Net-(P4-Pad7)") (class "Default")
      (node (ref "P4") (pin "7") (pinfunction "7_7") (pintype "passive"))
      (node (ref "U20") (pin "6") (pinfunction "6_6") (pintype "passive"))
    )
    (net (code "119") (name "Net-(P4-Pad8)") (class "Default")
      (node (ref "P4") (pin "8") (pinfunction "8_8") (pintype "passive"))
      (node (ref "U20") (pin "7") (pinfunction "7_7") (pintype "passive"))
    )
    (net (code "120") (name "Net-(P10-Pad2)") (class "Default")
      (node (ref "P10") (pin "2") (pinfunction "2_2") (pintype "passive"))
      (node (ref "U8") (pin "16") (pinfunction "16_16") (pintype "passive"))
    )
    (net (code "121") (name "Net-(P10-Pad3)") (class "Default")
      (node (ref "P10") (pin "3") (pinfunction "3_3") (pintype "passive"))
      (node (ref "U8") (pin "15") (pinfunction "15_15") (pintype "passive"))
    )
    (net (code "122") (name "Net-(P10-Pad4)") (class "Default")
      (node (ref "P10") (pin "4") (pinfunction "4_4") (pintype "passive"))
      (node (ref "U8") (pin "14") (pinfunction "14_14") (pintype "passive"))
    )
    (net (code "123") (name "Net-(P10-Pad5)") (class "Default")
      (node (ref "P10") (pin "5") (pinfunction "5_5") (pintype "passive"))
      (node (ref "U8") (pin "13") (pinfunction "13_13") (pintype "passive"))
    )
    (net (code "124") (name "Net-(P10-Pad6)") (class "Default")
      (node (ref "P10") (pin "6") (pinfunction "6_6") (pintype "passive"))
      (node (ref "U8") (pin "12") (pinfunction "12_12") (pintype "passive"))
    )
    (net (code "125") (name "Net-(P10-Pad7)") (class "Default")
      (node (ref "P10") (pin "7") (pinfunction "7_7") (pintype "passive"))
      (node (ref "U8") (pin "11") (pinfunction "11_11") (pintype "passive"))
    )
    (net (code "126") (name "Net-(P10-Pad8)") (class "Default")
      (node (ref "P10") (pin "8") (pinfunction "8_8") (pintype "passive"))
      (node (ref "U8") (pin "10") (pinfunction "10_10") (pintype "passive"))
    )
    (net (code "127") (name "Net-(P11-Pad2)") (class "Default")
      (node (ref "P11") (pin "2") (pinfunction "2_2") (pintype "passive"))
      (node (ref "U9") (pin "16") (pinfunction "16_16") (pintype "passive"))
    )
    (net (code "128") (name "Net-(P11-Pad3)") (class "Default")
      (node (ref "P11") (pin "3") (pinfunction "3_3") (pintype "passive"))
      (node (ref "U9") (pin "15") (pinfunction "15_15") (pintype "passive"))
    )
    (net (code "129") (name "Net-(P11-Pad4)") (class "Default")
      (node (ref "P11") (pin "4") (pinfunction "4_4") (pintype "passive"))
      (node (ref "U9") (pin "14") (pinfunction "14_14") (pintype "passive"))
    )
    (net (code "130") (name "Net-(P11-Pad5)") (class "Default")
      (node (ref "P11") (pin "5") (pinfunction "5_5") (pintype "passive"))
      (node (ref "U9") (pin "13") (pinfunction "13_13") (pintype "passive"))
    )
    (net (code "131") (name "Net-(P11-Pad6)") (class "Default")
      (node (ref "P11") (pin "6") (pinfunction "6_6") (pintype "passive"))
      (node (ref "U9") (pin "12") (pinfunction "12_12") (pintype "passive"))
    )
    (net (code "132") (name "Net-(P11-Pad7)") (class "Default")
      (node (ref "P11") (pin "7") (pinfunction "7_7") (pintype "passive"))
      (node (ref "U9") (pin "11") (pinfunction "11_11") (pintype "passive"))
    )
    (net (code "133") (name "Net-(P11-Pad8)") (class "Default")
      (node (ref "P11") (pin "8") (pinfunction "8_8") (pintype "passive"))
      (node (ref "U9") (pin "10") (pinfunction "10_10") (pintype "passive"))
    )
    (net (code "134") (name "Net-(P12-Pad2)") (class "Default")
      (node (ref "P12") (pin "2") (pinfunction "2_2") (pintype "passive"))
      (node (ref "U13") (pin "10") (pinfunction "10_10") (pintype "passive"))
    )
    (net (code "135") (name "Net-(P12-Pad3)") (class "Default")
      (node (ref "P12") (pin "3") (pinfunction "3_3") (pintype "passive"))
      (node (ref "U13") (pin "11") (pinfunction "11_11") (pintype "passive"))
    )
    (net (code "136") (name "Net-(P12-Pad4)") (class "Default")
      (node (ref "P12") (pin "4") (pinfunction "4_4") (pintype "passive"))
      (node (ref "U13") (pin "12") (pinfunction "12_12") (pintype "passive"))
    )
    (net (code "137") (name "Net-(P12-Pad5)") (class "Default")
      (node (ref "P12") (pin "5") (pinfunction "5_5") (pintype "passive"))
      (node (ref "U13") (pin "13") (pinfunction "13_13") (pintype "passive"))
    )
    (net (code "138") (name "Net-(P12-Pad6)") (class "Default")
      (node (ref "P12") (pin "6") (pinfunction "6_6") (pintype "passive"))
      (node (ref "U13") (pin "14") (pinfunction "14_14") (pintype "passive"))
    )
    (net (code "139") (name "Net-(P12-Pad7)") (class "Default")
      (node (ref "P12") (pin "7") (pinfunction "7_7") (pintype "passive"))
      (node (ref "U13") (pin "15") (pinfunction "15_15") (pintype "passive"))
    )
    (net (code "140") (name "Net-(P12-Pad8)") (class "Default")
      (node (ref "P12") (pin "8") (pinfunction "8_8") (pintype "passive"))
      (node (ref "U13") (pin "16") (pinfunction "16_16") (pintype "passive"))
    )
    (net (code "141") (name "Net-(P13-Pad2)") (class "Default")
      (node (ref "P13") (pin "2") (pinfunction "2_2") (pintype "passive"))
      (node (ref "U14") (pin "10") (pinfunction "10_10") (pintype "passive"))
    )
    (net (code "142") (name "Net-(P13-Pad3)") (class "Default")
      (node (ref "P13") (pin "3") (pinfunction "3_3") (pintype "passive"))
      (node (ref "U14") (pin "11") (pinfunction "11_11") (pintype "passive"))
    )
    (net (code "143") (name "Net-(P13-Pad4)") (class "Default")
      (node (ref "P13") (pin "4") (pinfunction "4_4") (pintype "passive"))
      (node (ref "U14") (pin "12") (pinfunction "12_12") (pintype "passive"))
    )
    (net (code "144") (name "Net-(P13-Pad5)") (class "Default")
      (node (ref "P13") (pin "5") (pinfunction "5_5") (pintype "passive"))
      (node (ref "U14") (pin "13") (pinfunction "13_13") (pintype "passive"))
    )
    (net (code "145") (name "Net-(P13-Pad6)") (class "Default")
      (node (ref "P13") (pin "6") (pinfunction "6_6") (pintype "passive"))
      (node (ref "U14") (pin "14") (pinfunction "14_14") (pintype "passive"))
    )
    (net (code "146") (name "Net-(P13-Pad7)") (class "Default")
      (node (ref "P13") (pin "7") (pinfunction "7_7") (pintype "passive"))
      (node (ref "U14") (pin "15") (pinfunction "15_15") (pintype "passive"))
    )
    (net (code "147") (name "Net-(P13-Pad8)") (class "Default")
      (node (ref "P13") (pin "8") (pinfunction "8_8") (pintype "passive"))
      (node (ref "U14") (pin "16") (pinfunction "16_16") (pintype "passive"))
    )
    (net (code "148") (name "Net-(P14-Pad2)") (class "Default")
      (node (ref "P14") (pin "2") (pinfunction "2_2") (pintype "passive"))
      (node (ref "U16") (pin "7") (pinfunction "7_7") (pintype "passive"))
    )
    (net (code "149") (name "Net-(P14-Pad3)") (class "Default")
      (node (ref "P14") (pin "3") (pinfunction "3_3") (pintype "passive"))
      (node (ref "U16") (pin "6") (pinfunction "6_6") (pintype "passive"))
    )
    (net (code "150") (name "Net-(P14-Pad4)") (class "Default")
      (node (ref "P14") (pin "4") (pinfunction "4_4") (pintype "passive"))
      (node (ref "U16") (pin "5") (pinfunction "5_5") (pintype "passive"))
    )
    (net (code "151") (name "Net-(P14-Pad5)") (class "Default")
      (node (ref "P14") (pin "5") (pinfunction "5_5") (pintype "passive"))
      (node (ref "U16") (pin "4") (pinfunction "4_4") (pintype "passive"))
    )
    (net (code "152") (name "Net-(P14-Pad6)") (class "Default")
      (node (ref "P14") (pin "6") (pinfunction "6_6") (pintype "passive"))
      (node (ref "U16") (pin "3") (pinfunction "3_3") (pintype "passive"))
    )
    (net (code "153") (name "Net-(P14-Pad7)") (class "Default")
      (node (ref "P14") (pin "7") (pinfunction "7_7") (pintype "passive"))
      (node (ref "U16") (pin "2") (pinfunction "2_2") (pintype "passive"))
    )
    (net (code "154") (name "Net-(P14-Pad8)") (class "Default")
      (node (ref "P14") (pin "8") (pinfunction "8_8") (pintype "passive"))
      (node (ref "U16") (pin "1") (pinfunction "1_1") (pintype "passive"))
    )
    (net (code "155") (name "Net-(P15-Pad2)") (class "Default")
      (node (ref "P15") (pin "2") (pinfunction "2_2") (pintype "passive"))
      (node (ref "U17") (pin "7") (pinfunction "7_7") (pintype "passive"))
    )
    (net (code "156") (name "Net-(P15-Pad3)") (class "Default")
      (node (ref "P15") (pin "3") (pinfunction "3_3") (pintype "passive"))
      (node (ref "U17") (pin "6") (pinfunction "6_6") (pintype "passive"))
    )
    (net (code "157") (name "Net-(P15-Pad4)") (class "Default")
      (node (ref "P15") (pin "4") (pinfunction "4_4") (pintype "passive"))
      (node (ref "U17") (pin "5") (pinfunction "5_5") (pintype "passive"))
    )
    (net (code "158") (name "Net-(P15-Pad5)") (class "Default")
      (node (ref "P15") (pin "5") (pinfunction "5_5") (pintype "passive"))
      (node (ref "U17") (pin "4") (pinfunction "4_4") (pintype "passive"))
    )
    (net (code "159") (name "Net-(P15-Pad6)") (class "Default")
      (node (ref "P15") (pin "6") (pinfunction "6_6") (pintype "passive"))
      (node (ref "U17") (pin "3") (pinfunction "3_3") (pintype "passive"))
    )
    (net (code "160") (name "Net-(P15-Pad7)") (class "Default")
      (node (ref "P15") (pin "7") (pinfunction "7_7") (pintype "passive"))
      (node (ref "U17") (pin "2") (pinfunction "2_2") (pintype "passive"))
    )
    (net (code "161") (name "Net-(P15-Pad8)") (class "Default")
      (node (ref "P15") (pin "8") (pinfunction "8_8") (pintype "passive"))
      (node (ref "U17") (pin "1") (pinfunction "1_1") (pintype "passive"))
    )
    (net (code "162") (name "Net-(P16-Pad2)") (class "Default")
      (node (ref "P16") (pin "2") (pinfunction "2_2") (pintype "passive"))
      (node (ref "U21") (pin "1") (pinfunction "1_1") (pintype "passive"))
    )
    (net (code "163") (name "Net-(P16-Pad3)") (class "Default")
      (node (ref "P16") (pin "3") (pinfunction "3_3") (pintype "passive"))
      (node (ref "U21") (pin "2") (pinfunction "2_2") (pintype "passive"))
    )
    (net (code "164") (name "Net-(P16-Pad4)") (class "Default")
      (node (ref "P16") (pin "4") (pinfunction "4_4") (pintype "passive"))
      (node (ref "U21") (pin "3") (pinfunction "3_3") (pintype "passive"))
    )
    (net (code "165") (name "Net-(P16-Pad5)") (class "Default")
      (node (ref "P16") (pin "5") (pinfunction "5_5") (pintype "passive"))
      (node (ref "U21") (pin "4") (pinfunction "4_4") (pintype "passive"))
    )
    (net (code "166") (name "Net-(P16-Pad6)") (class "Default")
      (node (ref "P16") (pin "6") (pinfunction "6_6") (pintype "passive"))
      (node (ref "U21") (pin "5") (pinfunction "5_5") (pintype "passive"))
    )
    (net (code "167") (name "Net-(P16-Pad7)") (class "Default")
      (node (ref "P16") (pin "7") (pinfunction "7_7") (pintype "passive"))
      (node (ref "U21") (pin "6") (pinfunction "6_6") (pintype "passive"))
    )
    (net (code "168") (name "Net-(P16-Pad8)") (class "Default")
      (node (ref "P16") (pin "8") (pinfunction "8_8") (pintype "passive"))
      (node (ref "U21") (pin "7") (pinfunction "7_7") (pintype "passive"))
    )
    (net (code "169") (name "Net-(P17-Pad2)") (class "Default")
      (node (ref "P17") (pin "2") (pinfunction "2_2") (pintype "passive"))
      (node (ref "U22") (pin "1") (pinfunction "1_1") (pintype "passive"))
    )
    (net (code "170") (name "Net-(P17-Pad3)") (class "Default")
      (node (ref "P17") (pin "3") (pinfunction "3_3") (pintype "passive"))
      (node (ref "U22") (pin "2") (pinfunction "2_2") (pintype "passive"))
    )
    (net (code "171") (name "Net-(P17-Pad4)") (class "Default")
      (node (ref "P17") (pin "4") (pinfunction "4_4") (pintype "passive"))
      (node (ref "U22") (pin "3") (pinfunction "3_3") (pintype "passive"))
    )
    (net (code "172") (name "Net-(P17-Pad5)") (class "Default")
      (node (ref "P17") (pin "5") (pinfunction "5_5") (pintype "passive"))
      (node (ref "U22") (pin "4") (pinfunction "4_4") (pintype "passive"))
    )
    (net (code "173") (name "Net-(P17-Pad6)") (class "Default")
      (node (ref "P17") (pin "6") (pinfunction "6_6") (pintype "passive"))
      (node (ref "U22") (pin "5") (pinfunction "5_5") (pintype "passive"))
    )
    (net (code "174") (name "Net-(P17-Pad7)") (class "Default")
      (node (ref "P17") (pin "7") (pinfunction "7_7") (pintype "passive"))
      (node (ref "U22") (pin "6") (pinfunction "6_6") (pintype "passive"))
    )
    (net (code "175") (name "Net-(P17-Pad8)") (class "Default")
      (node (ref "P17") (pin "8") (pinfunction "8_8") (pintype "passive"))
      (node (ref "U22") (pin "7") (pinfunction "7_7") (pintype "passive"))
    )
    (net (code "176") (name "VCC") (class "Default")
      (node (ref "C1") (pin "1") (pinfunction "1_1") (pintype "passive"))
      (node (ref "C10") (pin "1") (pinfunction "1_1") (pintype "passive"))
      (node (ref "C2") (pin "1") (pinfunction "1_1") (pintype "passive"))
      (node (ref "C7") (pin "1") (pinfunction "1_1") (pintype "passive"))
      (node (ref "C8") (pin "1") (pinfunction "1_1") (pintype "passive"))
      (node (ref "C9") (pin "1") (pinfunction "1_1") (pintype "passive"))
      (node (ref "U1") (pin "28") (pinfunction "VDD_28") (pintype "power_in"))
      (node (ref "U10") (pin "2") (pinfunction "A1_2") (pintype "input"))
      (node (ref "U10") (pin "28") (pinfunction "VDD_28") (pintype "power_in"))
      (node (ref "U11") (pin "28") (pinfunction "VDD_28") (pintype "power_in"))
      (node (ref "U11") (pin "3") (pinfunction "A2_3") (pintype "input"))
      (node (ref "U18") (pin "1") (pinfunction "A0_1") (pintype "input"))
      (node (ref "U18") (pin "2") (pinfunction "A1_2") (pintype "input"))
      (node (ref "U18") (pin "28") (pinfunction "VDD_28") (pintype "power_in"))
      (node (ref "U19") (pin "1") (pinfunction "A0_1") (pintype "input"))
      (node (ref "U19") (pin "28") (pinfunction "VDD_28") (pintype "power_in"))
      (node (ref "U19") (pin "3") (pinfunction "A2_3") (pintype "input"))
      (node (ref "U2") (pin "1") (pinfunction "A0_1") (pintype "input"))
      (node (ref "U2") (pin "28") (pinfunction "VDD_28") (pintype "power_in"))
    )
    (net (code "177") (name "unconnected-(U1-LED0-Pad6)") (class "Default")
      (node (ref "U1") (pin "6") (pinfunction "LED0_6") (pintype "output"))
    )
    (net (code "178") (name "unconnected-(U1-LED8-Pad15)") (class "Default")
      (node (ref "U1") (pin "15") (pinfunction "LED8_15") (pintype "output"))
    )
    (net (code "179") (name "unconnected-(U2-LED0-Pad6)") (class "Default")
      (node (ref "U2") (pin "6") (pinfunction "LED0_6") (pintype "output"))
    )
    (net (code "180") (name "unconnected-(U2-LED8-Pad15)") (class "Default")
      (node (ref "U2") (pin "15") (pinfunction "LED8_15") (pintype "output"))
    )
    (net (code "181") (name "unconnected-(U7-Pad8)") (class "Default")
      (node (ref "U7") (pin "8") (pinfunction "8_8") (pintype "passive"))
    )
    (net (code "182") (name "unconnected-(U7-Pad9)") (class "Default")
      (node (ref "U7") (pin "9") (pinfunction "9_9") (pintype "passive"))
    )
    (net (code "183") (name "unconnected-(U8-Pad8)") (class "Default")
      (node (ref "U8") (pin "8") (pinfunction "8_8") (pintype "passive"))
    )
    (net (code "184") (name "unconnected-(U8-Pad9)") (class "Default")
      (node (ref "U8") (pin "9") (pinfunction "9_9") (pintype "passive"))
    )
    (net (code "185") (name "unconnected-(U9-Pad8)") (class "Default")
      (node (ref "U9") (pin "8") (pinfunction "8_8") (pintype "passive"))
    )
    (net (code "186") (name "unconnected-(U9-Pad9)") (class "Default")
      (node (ref "U9") (pin "9") (pinfunction "9_9") (pintype "passive"))
    )
    (net (code "187") (name "unconnected-(U10-LED0-Pad6)") (class "Default")
      (node (ref "U10") (pin "6") (pinfunction "LED0_6") (pintype "output"))
    )
    (net (code "188") (name "unconnected-(U10-LED8-Pad15)") (class "Default")
      (node (ref "U10") (pin "15") (pinfunction "LED8_15") (pintype "output"))
    )
    (net (code "189") (name "unconnected-(U11-LED0-Pad6)") (class "Default")
      (node (ref "U11") (pin "6") (pinfunction "LED0_6") (pintype "output"))
    )
    (net (code "190") (name "unconnected-(U11-LED8-Pad15)") (class "Default")
      (node (ref "U11") (pin "15") (pinfunction "LED8_15") (pintype "output"))
    )
    (net (code "191") (name "unconnected-(U12-Pad8)") (class "Default")
      (node (ref "U12") (pin "8") (pinfunction "8_8") (pintype "passive"))
    )
    (net (code "192") (name "unconnected-(U12-Pad9)") (class "Default")
      (node (ref "U12") (pin "9") (pinfunction "9_9") (pintype "passive"))
    )
    (net (code "193") (name "unconnected-(U13-Pad8)") (class "Default")
      (node (ref "U13") (pin "8") (pinfunction "8_8") (pintype "passive"))
    )
    (net (code "194") (name "unconnected-(U13-Pad9)") (class "Default")
      (node (ref "U13") (pin "9") (pinfunction "9_9") (pintype "passive"))
    )
    (net (code "195") (name "unconnected-(U14-Pad8)") (class "Default")
      (node (ref "U14") (pin "8") (pinfunction "8_8") (pintype "passive"))
    )
    (net (code "196") (name "unconnected-(U14-Pad9)") (class "Default")
      (node (ref "U14") (pin "9") (pinfunction "9_9") (pintype "passive"))
    )
    (net (code "197") (name "unconnected-(U15-Pad8)") (class "Default")
      (node (ref "U15") (pin "8") (pinfunction "8_8") (pintype "passive"))
    )
    (net (code "198") (name "unconnected-(U15-Pad9)") (class "Default")
      (node (ref "U15") (pin "9") (pinfunction "9_9") (pintype "passive"))
    )
    (net (code "199") (name "unconnected-(U16-Pad8)") (class "Default")
      (node (ref "U16") (pin "8") (pinfunction "8_8") (pintype "passive"))
    )
    (net (code "200") (name "unconnected-(U16-Pad9)") (class "Default")
      (node (ref "U16") (pin "9") (pinfunction "9_9") (pintype "passive"))
    )
    (net (code "201") (name "unconnected-(U17-Pad8)") (class "Default")
      (node (ref "U17") (pin "8") (pinfunction "8_8") (pintype "passive"))
    )
    (net (code "202") (name "unconnected-(U17-Pad9)") (class "Default")
      (node (ref "U17") (pin "9") (pinfunction "9_9") (pintype "passive"))
    )
    (net (code "203") (name "unconnected-(U18-LED0-Pad6)") (class "Default")
      (node (ref "U18") (pin "6") (pinfunction "LED0_6") (pintype "output"))
    )
    (net (code "204") (name "unconnected-(U18-LED8-Pad15)") (class "Default")
      (node (ref "U18") (pin "15") (pinfunction "LED8_15") (pintype "output"))
    )
    (net (code "205") (name "unconnected-(U19-LED0-Pad6)") (class "Default")
      (node (ref "U19") (pin "6") (pinfunction "LED0_6") (pintype "output"))
    )
    (net (code "206") (name "unconnected-(U19-LED8-Pad15)") (class "Default")
      (node (ref "U19") (pin "15") (pinfunction "LED8_15") (pintype "output"))
    )
    (net (code "207") (name "unconnected-(U20-Pad8)") (class "Default")
      (node (ref "U20") (pin "8") (pinfunction "8_8") (pintype "passive"))
    )
    (net (code "208") (name "unconnected-(U20-Pad9)") (class "Default")
      (node (ref "U20") (pin "9") (pinfunction "9_9") (pintype "passive"))
    )
    (net (code "209") (name "unconnected-(U21-Pad8)") (class "Default")
      (node (ref "U21") (pin "8") (pinfunction "8_8") (pintype "passive"))
    )
    (net (code "210") (name "unconnected-(U21-Pad9)") (class "Default")
      (node (ref "U21") (pin "9") (pinfunction "9_9") (pintype "passive"))
    )
    (net (code "211") (name "unconnected-(U22-Pad8)") (class "Default")
      (node (ref "U22") (pin "8") (pinfunction "8_8") (pintype "passive"))
    )
    (net (code "212") (name "unconnected-(U22-Pad9)") (class "Default")
      (node (ref "U22") (pin "9") (pinfunction "9_9") (pintype "passive"))
    )
  )
)
